# Kernal64Cart.net
KiCad netlist of a schematic drawn in EAGLE
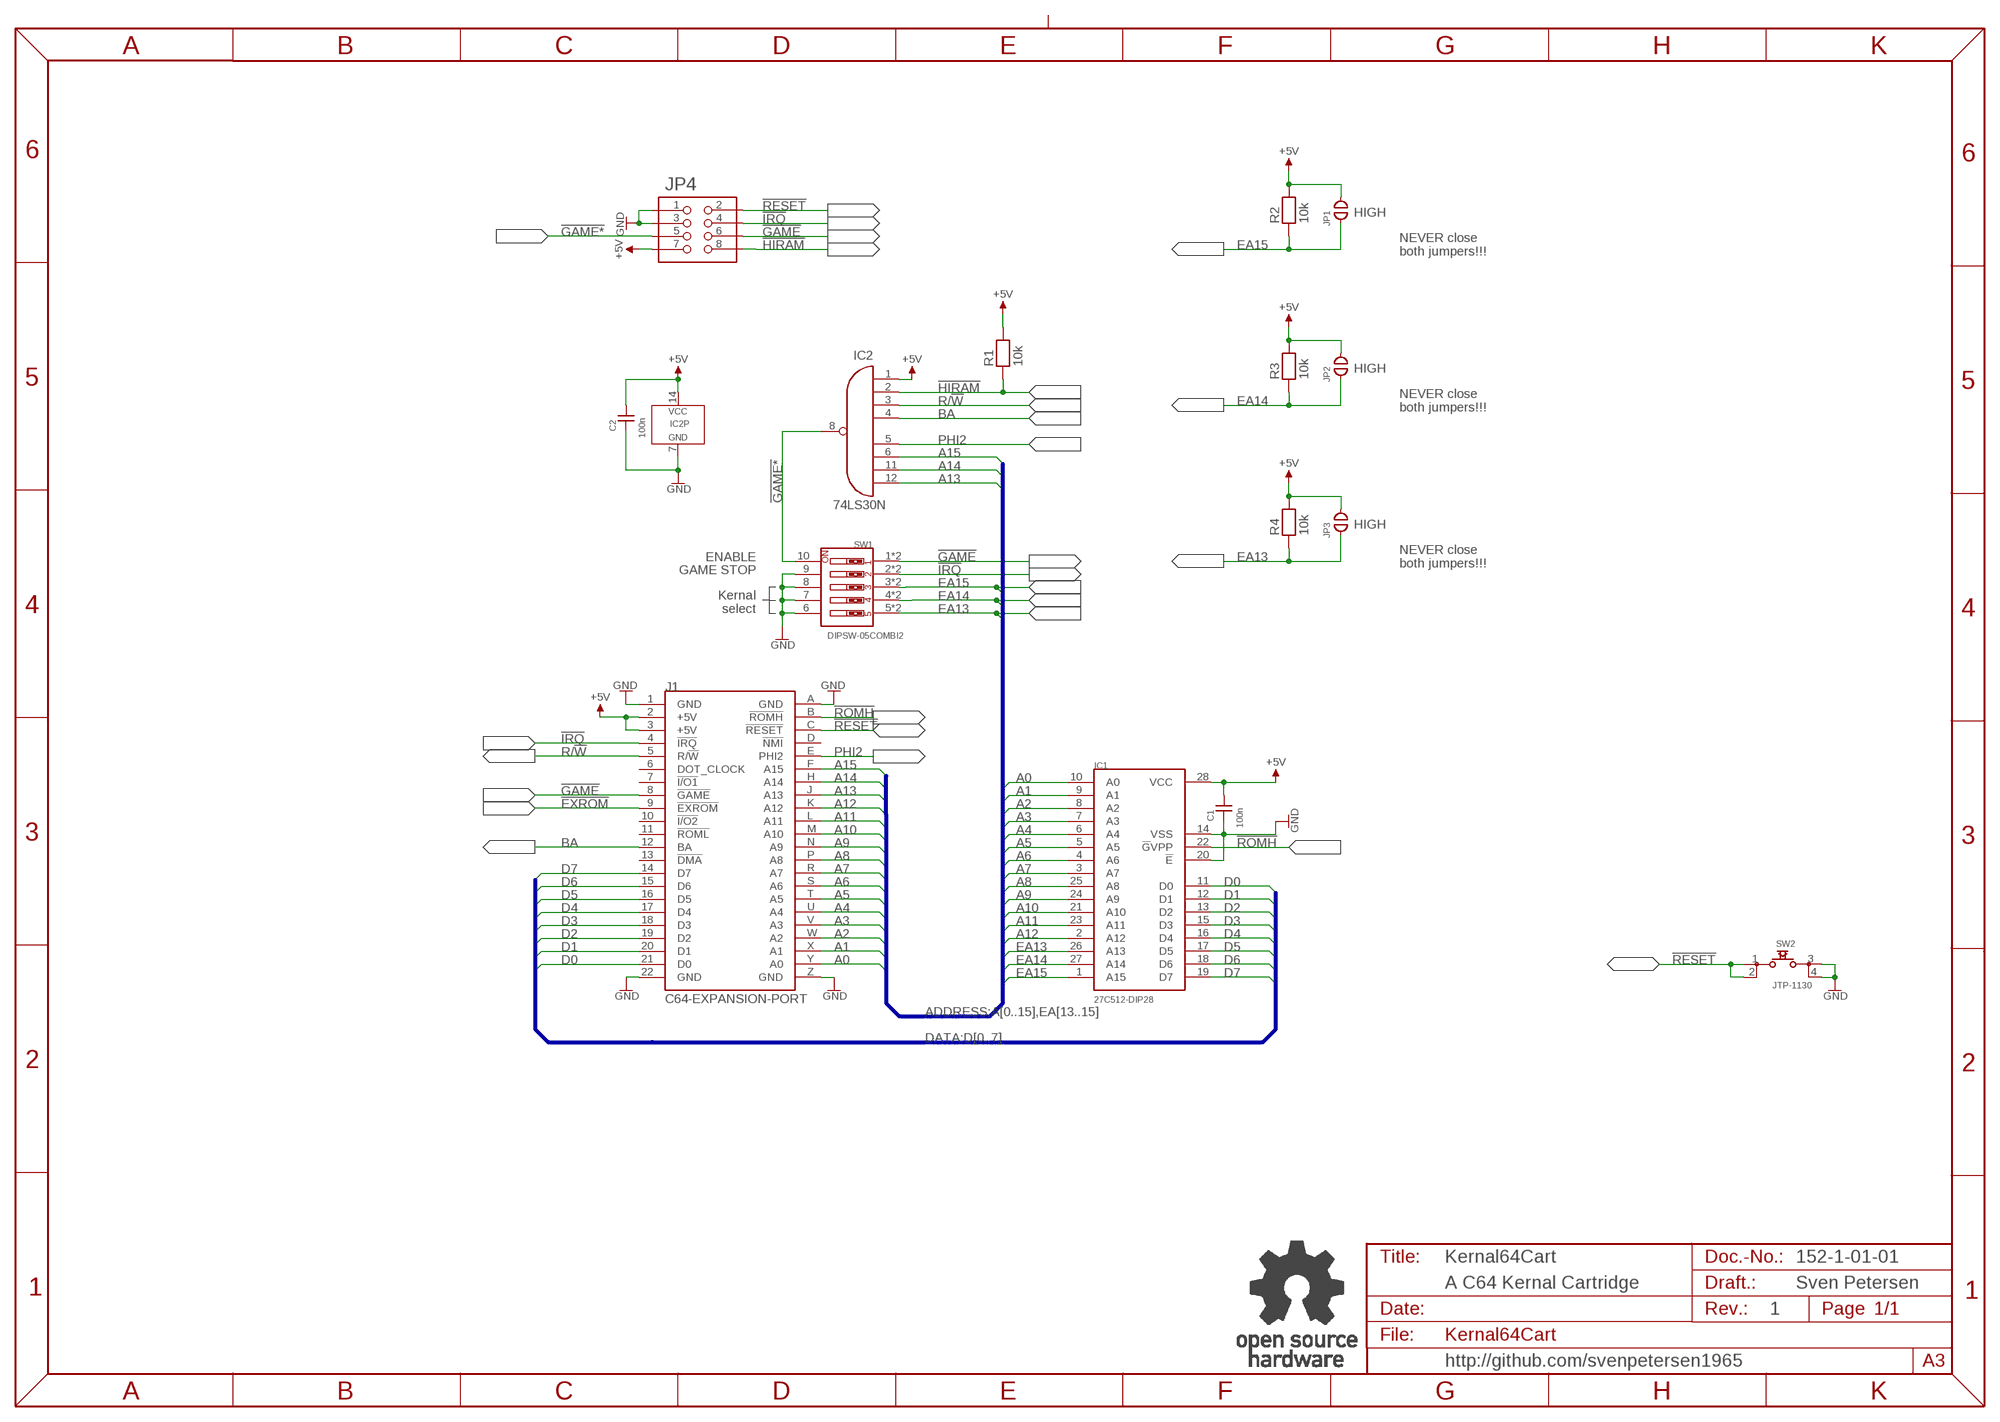
[diagram p0: schematic, sheet 1]

(export (version "E")
  (design (tool "Eeschema 10.0.6"))
  (components
    (comp (ref "C1")
      (value "100n")
      (footprint "eagle-import:C-2,5")
      (libsource (lib "eagle-import") (part "CAP01"))
    )
    (comp (ref "C2")
      (value "100n")
      (footprint "eagle-import:C-2,5")
      (libsource (lib "eagle-import") (part "CAP01"))
    )
    (comp (ref "IC1")
      (value "27C512-DIP28")
      (footprint "eagle-import:DIL28-6")
      (libsource (lib "eagle-import") (part "M27C512-DIP28"))
    )
    (comp (ref "IC2")
      (value "74LS30N")
      (footprint "eagle-import:DIL-14")
      (libsource (lib "eagle-import") (part "7430DIP"))
    )
    (comp (ref "J1")
      (value "C64-EXPANSION-PORT")
      (footprint "eagle-import:EXPANSIO_SQ")
      (libsource (lib "eagle-import") (part "C64-EXPANSIONPNARROW"))
    )
    (comp (ref "JP1")
      (value "OPEN")
      (footprint "eagle-import:CP_OP")
      (libsource (lib "eagle-import") (part "OPEN"))
    )
    (comp (ref "JP2")
      (value "OPEN")
      (footprint "eagle-import:CP_OP")
      (libsource (lib "eagle-import") (part "OPEN"))
    )
    (comp (ref "JP3")
      (value "OPEN")
      (footprint "eagle-import:CP_OP")
      (libsource (lib "eagle-import") (part "OPEN"))
    )
    (comp (ref "JP4")
      (value "PINHD-2X490°/MPE_088")
      (footprint "eagle-import:2X04_90_SERIES_088")
      (libsource (lib "eagle-import") (part "PINHD-2X490°/MPE_088"))
    )
    (comp (ref "R1")
      (value "10k")
      (footprint "eagle-import:R-10")
      (libsource (lib "eagle-import") (part "RES04"))
    )
    (comp (ref "R2")
      (value "10k")
      (footprint "eagle-import:R-10")
      (libsource (lib "eagle-import") (part "RES04"))
    )
    (comp (ref "R3")
      (value "10k")
      (footprint "eagle-import:R-10")
      (libsource (lib "eagle-import") (part "RES04"))
    )
    (comp (ref "R4")
      (value "10k")
      (footprint "eagle-import:R-10")
      (libsource (lib "eagle-import") (part "RES04"))
    )
    (comp (ref "SW1")
      (value "DIPSW-05COMBI2")
      (footprint "eagle-import:DIPSW-05V-COMBI2")
      (libsource (lib "eagle-import") (part "DIPSW-05COMBI2"))
    )
    (comp (ref "SW2")
      (value "JTP-1130")
      (footprint "eagle-import:JTP-1130")
      (libsource (lib "eagle-import") (part "JTP-1130"))
    )
    (comp (ref "U$50")
      (value "OPEN_SOURCE_HW")
      (footprint "eagle-import:OPENHW")
      (libsource (lib "eagle-import") (part "OPEN_SOURCE_HW"))
    )
  )
  (nets
    (net (code "9") (name "+5V") (class "Default")
      (node (ref "C1") (pin "2") (pinfunction "2_2") (pintype "passive"))
      (node (ref "C2") (pin "2") (pinfunction "2_2") (pintype "passive"))
      (node (ref "IC1") (pin "28") (pinfunction "VCC_28") (pintype "power_in"))
      (node (ref "IC2") (pin "1") (pinfunction "I0_1") (pintype "input"))
      (node (ref "IC2") (pin "14") (pinfunction "VCC_14") (pintype "bidirectional"))
      (node (ref "J1") (pin "2") (pinfunction "+5V_2") (pintype "power_in"))
      (node (ref "J1") (pin "3") (pinfunction "+5V_3") (pintype "power_in"))
      (node (ref "JP1") (pin "2") (pinfunction "2_2") (pintype "passive"))
      (node (ref "JP2") (pin "2") (pinfunction "2_2") (pintype "passive"))
      (node (ref "JP3") (pin "2") (pinfunction "2_2") (pintype "passive"))
      (node (ref "JP4") (pin "7") (pinfunction "7_7") (pintype "passive"))
      (node (ref "R1") (pin "2") (pinfunction "2_2") (pintype "passive"))
      (node (ref "R2") (pin "2") (pinfunction "2_2") (pintype "passive"))
      (node (ref "R3") (pin "2") (pinfunction "2_2") (pintype "passive"))
      (node (ref "R4") (pin "2") (pinfunction "2_2") (pintype "passive"))
    )
    (net (code "10") (name "/A0") (class "Default")
      (node (ref "IC1") (pin "10") (pinfunction "A0_10") (pintype "input"))
      (node (ref "J1") (pin "Y") (pinfunction "A0_Y") (pintype "bidirectional"))
    )
    (net (code "11") (name "/A1") (class "Default")
      (node (ref "IC1") (pin "9") (pinfunction "A1_9") (pintype "input"))
      (node (ref "J1") (pin "X") (pinfunction "A1_X") (pintype "bidirectional"))
    )
    (net (code "12") (name "/A2") (class "Default")
      (node (ref "IC1") (pin "8") (pinfunction "A2_8") (pintype "input"))
      (node (ref "J1") (pin "W") (pinfunction "A2_W") (pintype "bidirectional"))
    )
    (net (code "13") (name "/A3") (class "Default")
      (node (ref "IC1") (pin "7") (pinfunction "A3_7") (pintype "input"))
      (node (ref "J1") (pin "V") (pinfunction "A3_V") (pintype "bidirectional"))
    )
    (net (code "14") (name "/A4") (class "Default")
      (node (ref "IC1") (pin "6") (pinfunction "A4_6") (pintype "input"))
      (node (ref "J1") (pin "U") (pinfunction "A4_U") (pintype "bidirectional"))
    )
    (net (code "15") (name "/A5") (class "Default")
      (node (ref "IC1") (pin "5") (pinfunction "A5_5") (pintype "input"))
      (node (ref "J1") (pin "T") (pinfunction "A5_T") (pintype "bidirectional"))
    )
    (net (code "16") (name "/A6") (class "Default")
      (node (ref "IC1") (pin "4") (pinfunction "A6_4") (pintype "input"))
      (node (ref "J1") (pin "S") (pinfunction "A6_S") (pintype "bidirectional"))
    )
    (net (code "17") (name "/A7") (class "Default")
      (node (ref "IC1") (pin "3") (pinfunction "A7_3") (pintype "input"))
      (node (ref "J1") (pin "R") (pinfunction "A7_R") (pintype "bidirectional"))
    )
    (net (code "18") (name "/A8") (class "Default")
      (node (ref "IC1") (pin "25") (pinfunction "A8_25") (pintype "input"))
      (node (ref "J1") (pin "P") (pinfunction "A8_P") (pintype "bidirectional"))
    )
    (net (code "19") (name "/A9") (class "Default")
      (node (ref "IC1") (pin "24") (pinfunction "A9_24") (pintype "input"))
      (node (ref "J1") (pin "N") (pinfunction "A9_N") (pintype "bidirectional"))
    )
    (net (code "20") (name "/A10") (class "Default")
      (node (ref "IC1") (pin "21") (pinfunction "A10_21") (pintype "input"))
      (node (ref "J1") (pin "M") (pinfunction "A10_M") (pintype "bidirectional"))
    )
    (net (code "21") (name "/A11") (class "Default")
      (node (ref "IC1") (pin "23") (pinfunction "A11_23") (pintype "input"))
      (node (ref "J1") (pin "L") (pinfunction "A11_L") (pintype "bidirectional"))
    )
    (net (code "22") (name "/A12") (class "Default")
      (node (ref "IC1") (pin "2") (pinfunction "A12_2") (pintype "input"))
      (node (ref "J1") (pin "K") (pinfunction "A12_K") (pintype "bidirectional"))
    )
    (net (code "23") (name "/A13") (class "Default")
      (node (ref "IC2") (pin "12") (pinfunction "I7_12") (pintype "input"))
      (node (ref "J1") (pin "J") (pinfunction "A13_J") (pintype "bidirectional"))
    )
    (net (code "24") (name "/A14") (class "Default")
      (node (ref "IC2") (pin "11") (pinfunction "I6_11") (pintype "input"))
      (node (ref "J1") (pin "H") (pinfunction "A14_H") (pintype "bidirectional"))
    )
    (net (code "25") (name "/A15") (class "Default")
      (node (ref "IC2") (pin "6") (pinfunction "I5_6") (pintype "input"))
      (node (ref "J1") (pin "F") (pinfunction "A15_F") (pintype "bidirectional"))
    )
    (net (code "26") (name "/BA") (class "Default")
      (node (ref "IC2") (pin "4") (pinfunction "I3_4") (pintype "input"))
      (node (ref "J1") (pin "12") (pinfunction "BA_12") (pintype "output"))
    )
    (net (code "27") (name "/D0") (class "Default")
      (node (ref "IC1") (pin "11") (pinfunction "D0_11") (pintype "bidirectional"))
      (node (ref "J1") (pin "21") (pinfunction "D0_21") (pintype "bidirectional"))
    )
    (net (code "28") (name "/D1") (class "Default")
      (node (ref "IC1") (pin "12") (pinfunction "D1_12") (pintype "bidirectional"))
      (node (ref "J1") (pin "20") (pinfunction "D1_20") (pintype "bidirectional"))
    )
    (net (code "29") (name "/D2") (class "Default")
      (node (ref "IC1") (pin "13") (pinfunction "D2_13") (pintype "bidirectional"))
      (node (ref "J1") (pin "19") (pinfunction "D2_19") (pintype "bidirectional"))
    )
    (net (code "30") (name "/D3") (class "Default")
      (node (ref "IC1") (pin "15") (pinfunction "D3_15") (pintype "bidirectional"))
      (node (ref "J1") (pin "18") (pinfunction "D3_18") (pintype "bidirectional"))
    )
    (net (code "31") (name "/D4") (class "Default")
      (node (ref "IC1") (pin "16") (pinfunction "D4_16") (pintype "bidirectional"))
      (node (ref "J1") (pin "17") (pinfunction "D4_17") (pintype "bidirectional"))
    )
    (net (code "32") (name "/D5") (class "Default")
      (node (ref "IC1") (pin "17") (pinfunction "D5_17") (pintype "bidirectional"))
      (node (ref "J1") (pin "16") (pinfunction "D5_16") (pintype "bidirectional"))
    )
    (net (code "33") (name "/D6") (class "Default")
      (node (ref "IC1") (pin "18") (pinfunction "D6_18") (pintype "bidirectional"))
      (node (ref "J1") (pin "15") (pinfunction "D6_15") (pintype "bidirectional"))
    )
    (net (code "34") (name "/D7") (class "Default")
      (node (ref "IC1") (pin "19") (pinfunction "D7_19") (pintype "bidirectional"))
      (node (ref "J1") (pin "14") (pinfunction "D7_14") (pintype "bidirectional"))
    )
    (net (code "36") (name "/EA13") (class "Default")
      (node (ref "IC1") (pin "26") (pinfunction "A13_26") (pintype "input"))
      (node (ref "JP3") (pin "1") (pinfunction "1_1") (pintype "passive"))
      (node (ref "R4") (pin "1") (pinfunction "1_1") (pintype "passive"))
      (node (ref "SW1") (pin "5") (pinfunction "5_5") (pintype "passive"))
      (node (ref "SW1") (pin "5A") (pinfunction "5_5A") (pintype "passive"))
    )
    (net (code "37") (name "/EA14") (class "Default")
      (node (ref "IC1") (pin "27") (pinfunction "A14_27") (pintype "input"))
      (node (ref "JP2") (pin "1") (pinfunction "1_1") (pintype "passive"))
      (node (ref "R3") (pin "1") (pinfunction "1_1") (pintype "passive"))
      (node (ref "SW1") (pin "4") (pinfunction "4_4") (pintype "passive"))
      (node (ref "SW1") (pin "4A") (pinfunction "4_4A") (pintype "passive"))
    )
    (net (code "38") (name "/EA15") (class "Default")
      (node (ref "IC1") (pin "1") (pinfunction "A15_1") (pintype "input"))
      (node (ref "JP1") (pin "1") (pinfunction "1_1") (pintype "passive"))
      (node (ref "R2") (pin "1") (pinfunction "1_1") (pintype "passive"))
      (node (ref "SW1") (pin "3") (pinfunction "3_3") (pintype "passive"))
      (node (ref "SW1") (pin "3A") (pinfunction "3_3A") (pintype "passive"))
    )
    (net (code "39") (name "/PHI2") (class "Default")
      (node (ref "IC2") (pin "5") (pinfunction "I4_5") (pintype "input"))
      (node (ref "J1") (pin "E") (pinfunction "PHI2_E") (pintype "output"))
    )
    (net (code "40") (name "/R{slash}~{W}") (class "Default")
      (node (ref "IC2") (pin "3") (pinfunction "I2_3") (pintype "input"))
      (node (ref "J1") (pin "5") (pinfunction "R/~{W}_5") (pintype "output"))
    )
    (net (code "42") (name "/~{EXROM}") (class "Default")
      (node (ref "J1") (pin "9") (pinfunction "~{EXROM}_9") (pintype "input"))
    )
    (net (code "43") (name "/~{GAME*}") (class "Default")
      (node (ref "IC2") (pin "8") (pinfunction "O_8") (pintype "output"))
      (node (ref "JP4") (pin "5") (pinfunction "5_5") (pintype "passive"))
      (node (ref "SW1") (pin "10") (pinfunction "10_10") (pintype "passive"))
    )
    (net (code "44") (name "/~{GAME}") (class "Default")
      (node (ref "J1") (pin "8") (pinfunction "~{GAME}_8") (pintype "input"))
      (node (ref "JP4") (pin "6") (pinfunction "6_6") (pintype "passive"))
      (node (ref "SW1") (pin "1") (pinfunction "1_1") (pintype "passive"))
      (node (ref "SW1") (pin "1A") (pinfunction "1_1A") (pintype "passive"))
    )
    (net (code "45") (name "/~{HIRAM}") (class "Default")
      (node (ref "IC2") (pin "2") (pinfunction "I1_2") (pintype "input"))
      (node (ref "JP4") (pin "8") (pinfunction "8_8") (pintype "passive"))
      (node (ref "R1") (pin "1") (pinfunction "1_1") (pintype "passive"))
    )
    (net (code "46") (name "/~{IRQ}") (class "Default")
      (node (ref "J1") (pin "4") (pinfunction "~{IRQ}_4") (pintype "input"))
      (node (ref "JP4") (pin "4") (pinfunction "4_4") (pintype "passive"))
      (node (ref "SW1") (pin "2") (pinfunction "2_2") (pintype "passive"))
      (node (ref "SW1") (pin "2A") (pinfunction "2_2A") (pintype "passive"))
    )
    (net (code "47") (name "/~{RESET}") (class "Default")
      (node (ref "J1") (pin "C") (pinfunction "~{RESET}_C") (pintype "open_collector"))
      (node (ref "JP4") (pin "2") (pinfunction "2_2") (pintype "passive"))
      (node (ref "SW2") (pin "1") (pinfunction "1_1") (pintype "passive"))
      (node (ref "SW2") (pin "2") (pinfunction "2_2") (pintype "passive"))
    )
    (net (code "48") (name "/~{ROMH}") (class "Default")
      (node (ref "IC1") (pin "22") (pinfunction "~{G}VPP_22") (pintype "input"))
      (node (ref "J1") (pin "B") (pinfunction "~{ROMH}_B") (pintype "output"))
    )
    (net (code "49") (name "GND") (class "Default")
      (node (ref "C1") (pin "1") (pinfunction "1_1") (pintype "passive"))
      (node (ref "C2") (pin "1") (pinfunction "1_1") (pintype "passive"))
      (node (ref "IC1") (pin "14") (pinfunction "VSS_14") (pintype "power_in"))
      (node (ref "IC1") (pin "20") (pinfunction "~{E}_20") (pintype "input"))
      (node (ref "IC2") (pin "7") (pinfunction "GND_7") (pintype "bidirectional"))
      (node (ref "J1") (pin "1") (pinfunction "GND_1") (pintype "power_in"))
      (node (ref "J1") (pin "22") (pinfunction "GND_22") (pintype "power_in"))
      (node (ref "J1") (pin "A") (pinfunction "GND_A") (pintype "power_in"))
      (node (ref "J1") (pin "Z") (pinfunction "GND_Z") (pintype "power_in"))
      (node (ref "JP4") (pin "1") (pinfunction "1_1") (pintype "passive"))
      (node (ref "JP4") (pin "3") (pinfunction "3_3") (pintype "passive"))
      (node (ref "SW1") (pin "6") (pinfunction "6_6") (pintype "passive"))
      (node (ref "SW1") (pin "7") (pinfunction "7_7") (pintype "passive"))
      (node (ref "SW1") (pin "8") (pinfunction "8_8") (pintype "passive"))
      (node (ref "SW1") (pin "9") (pinfunction "9_9") (pintype "passive"))
      (node (ref "SW2") (pin "3") (pinfunction "3_3") (pintype "passive"))
      (node (ref "SW2") (pin "4") (pinfunction "4_4") (pintype "passive"))
    )
    (net (code "50") (name "unconnected-(J1-DOT_CLOCK-Pad6)") (class "Default")
      (node (ref "J1") (pin "6") (pinfunction "DOT_CLOCK_6") (pintype "output"))
    )
    (net (code "51") (name "unconnected-(J1-~{DMA}-Pad13)") (class "Default")
      (node (ref "J1") (pin "13") (pinfunction "~{DMA}_13") (pintype "input"))
    )
    (net (code "52") (name "unconnected-(J1-~{I{slash}O1}-Pad7)") (class "Default")
      (node (ref "J1") (pin "7") (pinfunction "~{I/O1}_7") (pintype "output"))
    )
    (net (code "53") (name "unconnected-(J1-~{I{slash}O2}-Pad10)") (class "Default")
      (node (ref "J1") (pin "10") (pinfunction "~{I/O2}_10") (pintype "output"))
    )
    (net (code "54") (name "unconnected-(J1-~{NMI}-PadD)") (class "Default")
      (node (ref "J1") (pin "D") (pinfunction "~{NMI}_D") (pintype "input"))
    )
    (net (code "55") (name "unconnected-(J1-~{ROML}-Pad11)") (class "Default")
      (node (ref "J1") (pin "11") (pinfunction "~{ROML}_11") (pintype "output"))
    )
  )
)
